# AD7606.net
KiCad netlist of a schematic drawn in Altium Designer
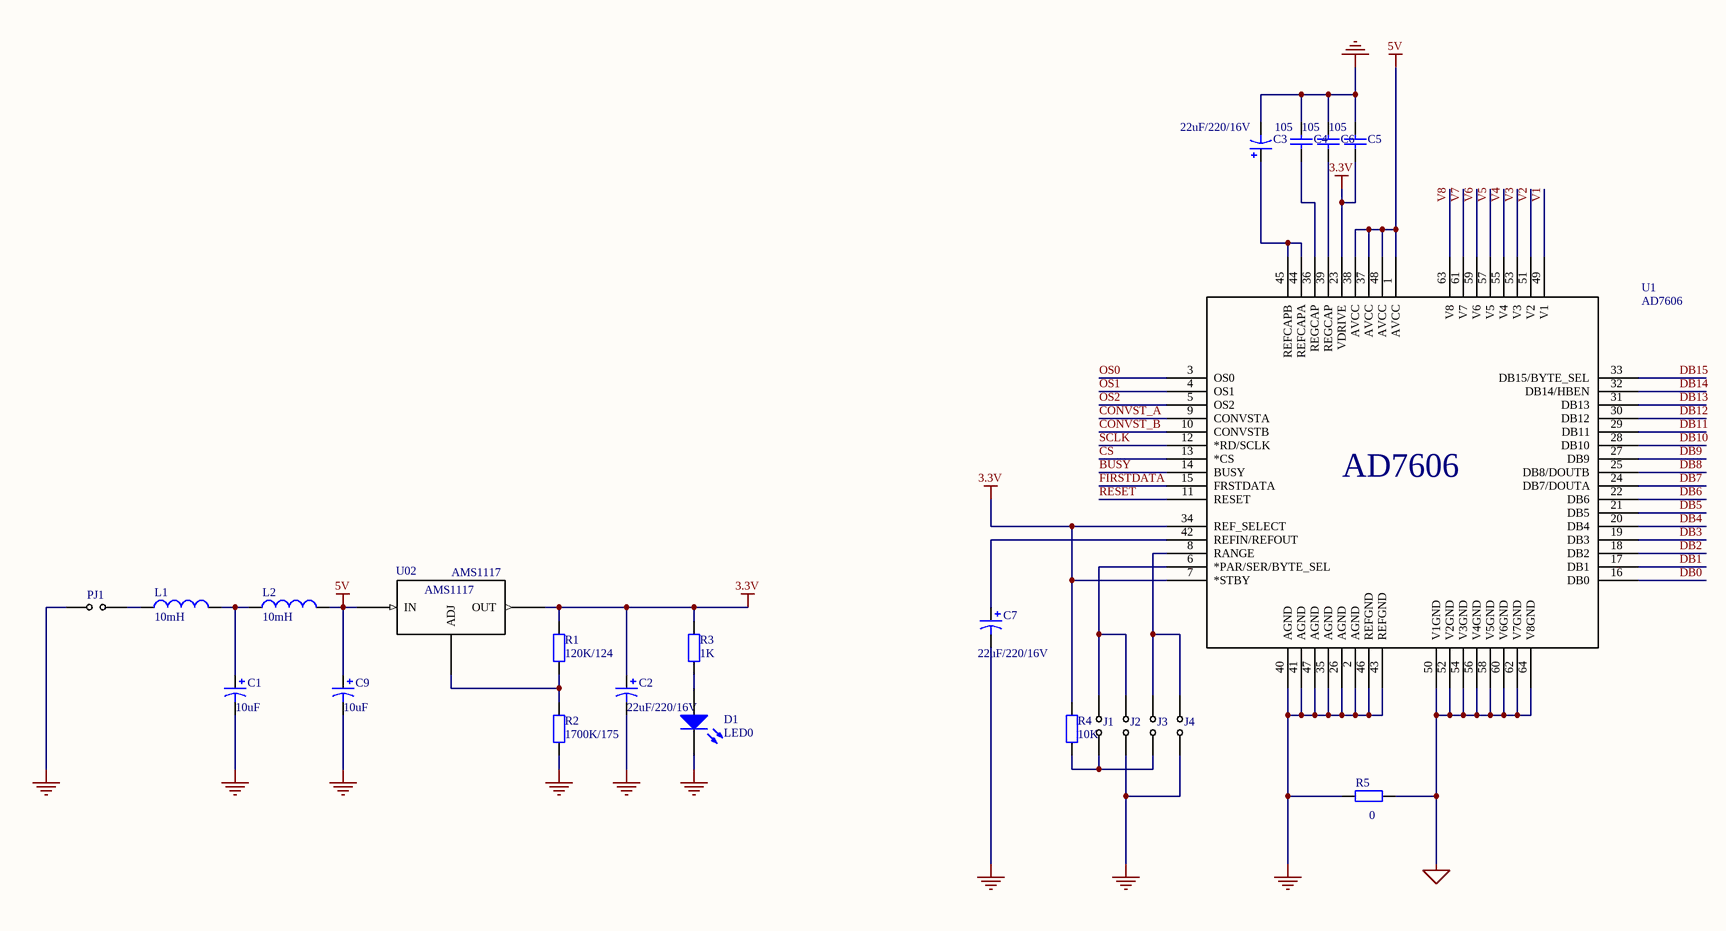
[diagram p0: AD7606.SchDoc]

(export (version "E")
  (design (tool "Eeschema 10.0.6"))
  (components
    (comp (ref "C1")
      (value "10uF")
      (footprint "TCAP_SMD_2312_6032-28_C_M")
      (description "Polarized Capacitor (Radial)")
      (fields (field (name "Comment") "Cap Pol1") (field (name "PUBLISHER") "Altium Limited"))
      (libsource (lib "Miscellaneous Devices") (part "Cap Pol1"))
    )
    (comp (ref "C2")
      (value "22uF/220/16V")
      (footprint "TCAP_SMD_2312_6032-28_C_M")
      (description "Polarized Capacitor (Radial)")
      (fields (field (name "Comment") "Cap Pol1") (field (name "PUBLISHER") "Altium Limited"))
      (libsource (lib "Miscellaneous Devices") (part "Cap Pol1"))
    )
    (comp (ref "C3")
      (value "22uF/220/16V")
      (footprint "TCAP_SMD_2312_6032-28_C_M")
      (description "Polarized Capacitor (Radial)")
      (fields (field (name "Comment") "Cap Pol1") (field (name "PUBLISHER") "Altium Limited"))
      (libsource (lib "Miscellaneous Devices") (part "Cap Pol1"))
    )
    (comp (ref "C4")
      (value "105")
      (footprint "CAP_SMD_1206_3216_M")
      (description "Capacitor")
      (fields (field (name "Comment") "Cap") (field (name "PUBLISHER") "Altium Limited"))
      (libsource (lib "Miscellaneous Devices") (part "Cap"))
    )
    (comp (ref "C5")
      (value "105")
      (footprint "CAP_SMD_1206_3216_M")
      (description "Capacitor")
      (fields (field (name "Comment") "Cap") (field (name "PUBLISHER") "Altium Limited"))
      (libsource (lib "Miscellaneous Devices") (part "Cap"))
    )
    (comp (ref "C6")
      (value "105")
      (footprint "CAP_SMD_1206_3216_M")
      (description "Capacitor")
      (fields (field (name "Comment") "Cap") (field (name "PUBLISHER") "Altium Limited"))
      (libsource (lib "Miscellaneous Devices") (part "Cap"))
    )
    (comp (ref "C7")
      (value "22uF/220/16V")
      (footprint "TCAP_SMD_2312_6032-28_C_M")
      (description "Polarized Capacitor (Radial)")
      (fields (field (name "Comment") "Cap Pol1") (field (name "PUBLISHER") "Altium Limited"))
      (libsource (lib "Miscellaneous Devices") (part "Cap Pol1"))
    )
    (comp (ref "C9")
      (value "10uF")
      (footprint "TCAP_SMD_2312_6032-28_C_M")
      (description "Polarized Capacitor (Radial)")
      (fields (field (name "Comment") "Cap Pol1") (field (name "PUBLISHER") "Altium Limited"))
      (libsource (lib "Miscellaneous Devices") (part "Cap Pol1"))
    )
    (comp (ref "D1")
      (value "LED0")
      (footprint "LED_SMD_0805_2012_M")
      (description "Typical INFRARED GaAs LED")
      (fields (field (name "PUBLISHER") "Altium Limited"))
      (libsource (lib "Miscellaneous Devices") (part "LED0"))
    )
    (comp (ref "J1") (value "head2") (footprint "HDR1X2") (libsource (lib "") (part "head2_1")))
    (comp (ref "J2") (value "head2") (footprint "HDR1X2") (libsource (lib "connectLib") (part "head2")))
    (comp (ref "J3") (value "head2") (footprint "HDR1X2") (libsource (lib "connectLib") (part "head2")))
    (comp (ref "J4") (value "head2") (footprint "HDR1X2") (libsource (lib "connectLib") (part "head2")))
    (comp (ref "L1")
      (value "10mH")
      (footprint "RES_SMD_0805_2012_M")
      (description "Inductor")
      (fields (field (name "PUBLISHER") "Altium Limited"))
      (libsource (lib "Miscellaneous Devices") (part "Inductor"))
    )
    (comp (ref "L2")
      (value "10mH")
      (footprint "RES_SMD_0805_2012_M")
      (description "Inductor")
      (fields (field (name "PUBLISHER") "Altium Limited"))
      (libsource (lib "Miscellaneous Devices") (part "Inductor"))
    )
    (comp (ref "PJ1") (value "head2") (footprint "HDR1X2") (libsource (lib "connectLib") (part "head2")))
    (comp (ref "R1")
      (value "120K/124")
      (footprint "RES_SMD_1206_3216_M")
      (description "Resistor")
      (fields (field (name "Comment") "Res2") (field (name "PUBLISHER") "Altium Limited"))
      (libsource (lib "") (part "Res2_1"))
    )
    (comp (ref "R2")
      (value "1700K/175")
      (footprint "RES_SMD_1206_3216_M")
      (description "Resistor")
      (fields (field (name "Comment") "Res2") (field (name "PUBLISHER") "Altium Limited"))
      (libsource (lib "") (part "Res2_1"))
    )
    (comp (ref "R3")
      (value "1K")
      (footprint "RES_SMD_1206_3216_M")
      (description "Resistor")
      (fields (field (name "Comment") "Res2") (field (name "PUBLISHER") "Altium Limited"))
      (libsource (lib "Miscellaneous Devices") (part "Res2"))
    )
    (comp (ref "R4")
      (value "10K")
      (footprint "RES_SMD_1206_3216_M")
      (description "Resistor")
      (fields (field (name "Comment") "Res2") (field (name "PUBLISHER") "Altium Limited"))
      (libsource (lib "") (part "Res2_1"))
    )
    (comp (ref "R5")
      (value "0")
      (footprint "RES_SMD_1206_3216_M")
      (description "Resistor")
      (fields (field (name "Comment") "Res2") (field (name "PUBLISHER") "Altium Limited"))
      (libsource (lib "") (part "Res2_2"))
    )
    (comp (ref "U1") (value "AD7606") (footprint "AD7606") (libsource (lib "multisupport") (part "AD7606")))
    (comp (ref "U02")
      (value "AMS1117")
      (footprint "SOT230P700X180-4N")
      (libsource (lib "chipslib") (part "AMS1117"))
    )
  )
  (nets
    (net (code "1") (name "/BUSY") (class "Default")
      (node (ref "U1") (pin "14") (pinfunction "BUSY_14") (pintype "passive"))
    )
    (net (code "2") (name "/CONVST_A") (class "Default")
      (node (ref "U1") (pin "9") (pinfunction "CONVSTA_9") (pintype "passive"))
    )
    (net (code "3") (name "/CONVST_B") (class "Default")
      (node (ref "U1") (pin "10") (pinfunction "CONVSTB_10") (pintype "passive"))
    )
    (net (code "4") (name "/CS") (class "Default")
      (node (ref "U1") (pin "13") (pinfunction "*CS_13") (pintype "passive"))
    )
    (net (code "5") (name "/DB0") (class "Default")
      (node (ref "U1") (pin "16") (pinfunction "DB0_16") (pintype "passive"))
    )
    (net (code "6") (name "/DB1") (class "Default")
      (node (ref "U1") (pin "17") (pinfunction "DB1_17") (pintype "passive"))
    )
    (net (code "7") (name "/DB2") (class "Default")
      (node (ref "U1") (pin "18") (pinfunction "DB2_18") (pintype "passive"))
    )
    (net (code "8") (name "/DB3") (class "Default")
      (node (ref "U1") (pin "19") (pinfunction "DB3_19") (pintype "passive"))
    )
    (net (code "9") (name "/DB4") (class "Default")
      (node (ref "U1") (pin "20") (pinfunction "DB4_20") (pintype "passive"))
    )
    (net (code "10") (name "/DB5") (class "Default")
      (node (ref "U1") (pin "21") (pinfunction "DB5_21") (pintype "passive"))
    )
    (net (code "11") (name "/DB6") (class "Default")
      (node (ref "U1") (pin "22") (pinfunction "DB6_22") (pintype "passive"))
    )
    (net (code "12") (name "/DB7") (class "Default")
      (node (ref "U1") (pin "24") (pinfunction "DB7/DOUTA_24") (pintype "passive"))
    )
    (net (code "13") (name "/DB8") (class "Default")
      (node (ref "U1") (pin "25") (pinfunction "DB8/DOUTB_25") (pintype "passive"))
    )
    (net (code "14") (name "/DB9") (class "Default")
      (node (ref "U1") (pin "27") (pinfunction "DB9_27") (pintype "passive"))
    )
    (net (code "15") (name "/DB10") (class "Default")
      (node (ref "U1") (pin "28") (pinfunction "DB10_28") (pintype "passive"))
    )
    (net (code "16") (name "/DB11") (class "Default")
      (node (ref "U1") (pin "29") (pinfunction "DB11_29") (pintype "passive"))
    )
    (net (code "17") (name "/DB12") (class "Default")
      (node (ref "U1") (pin "30") (pinfunction "DB12_30") (pintype "passive"))
    )
    (net (code "18") (name "/DB13") (class "Default")
      (node (ref "U1") (pin "31") (pinfunction "DB13_31") (pintype "passive"))
    )
    (net (code "19") (name "/DB14") (class "Default")
      (node (ref "U1") (pin "32") (pinfunction "DB14/HBEN_32") (pintype "passive"))
    )
    (net (code "20") (name "/DB15") (class "Default")
      (node (ref "U1") (pin "33") (pinfunction "DB15/BYTE_SEL_33") (pintype "passive"))
    )
    (net (code "21") (name "/FIRSTDATA") (class "Default")
      (node (ref "U1") (pin "15") (pinfunction "FRSTDATA_15") (pintype "passive"))
    )
    (net (code "22") (name "/OS0") (class "Default")
      (node (ref "U1") (pin "3") (pinfunction "OS0_3") (pintype "passive"))
    )
    (net (code "23") (name "/OS1") (class "Default")
      (node (ref "U1") (pin "4") (pinfunction "OS1_4") (pintype "passive"))
    )
    (net (code "24") (name "/OS2") (class "Default")
      (node (ref "U1") (pin "5") (pinfunction "OS2_5") (pintype "passive"))
    )
    (net (code "25") (name "/RESET") (class "Default")
      (node (ref "U1") (pin "11") (pinfunction "RESET_11") (pintype "passive"))
    )
    (net (code "26") (name "/SCLK") (class "Default")
      (node (ref "U1") (pin "12") (pinfunction "*RD/SCLK_12") (pintype "passive"))
    )
    (net (code "27") (name "/V1") (class "Default")
      (node (ref "U1") (pin "49") (pinfunction "V1_49") (pintype "passive"))
    )
    (net (code "28") (name "/V2") (class "Default")
      (node (ref "U1") (pin "51") (pinfunction "V2_51") (pintype "passive"))
    )
    (net (code "29") (name "/V3") (class "Default")
      (node (ref "U1") (pin "53") (pinfunction "V3_53") (pintype "passive"))
    )
    (net (code "30") (name "/V4") (class "Default")
      (node (ref "U1") (pin "55") (pinfunction "V4_55") (pintype "passive"))
    )
    (net (code "31") (name "/V5") (class "Default")
      (node (ref "U1") (pin "57") (pinfunction "V5_57") (pintype "passive"))
    )
    (net (code "32") (name "/V6") (class "Default")
      (node (ref "U1") (pin "59") (pinfunction "V6_59") (pintype "passive"))
    )
    (net (code "33") (name "/V7") (class "Default")
      (node (ref "U1") (pin "61") (pinfunction "V7_61") (pintype "passive"))
    )
    (net (code "34") (name "/V8") (class "Default")
      (node (ref "U1") (pin "63") (pinfunction "V8_63") (pintype "passive"))
    )
    (net (code "35") (name "3.3V") (class "Default")
      (node (ref "C2") (pin "1") (pinfunction "1_1") (pintype "passive"))
      (node (ref "C5") (pin "1") (pinfunction "1_1") (pintype "passive"))
      (node (ref "R1") (pin "2") (pinfunction "2_2") (pintype "passive"))
      (node (ref "R3") (pin "1") (pinfunction "1_1") (pintype "passive"))
      (node (ref "R4") (pin "2") (pinfunction "2_2") (pintype "passive"))
      (node (ref "U02") (pin "2") (pinfunction "OUT_2") (pintype "output"))
      (node (ref "U1") (pin "23") (pinfunction "VDRIVE_23") (pintype "passive"))
      (node (ref "U1") (pin "34") (pinfunction "REF_SELECT_34") (pintype "passive"))
      (node (ref "U1") (pin "7") (pinfunction "*STBY_7") (pintype "passive"))
    )
    (net (code "36") (name "5V") (class "Default")
      (node (ref "C9") (pin "1") (pinfunction "1_1") (pintype "passive"))
      (node (ref "L2") (pin "2") (pinfunction "2_2") (pintype "passive"))
      (node (ref "U02") (pin "3") (pinfunction "IN_3") (pintype "input"))
      (node (ref "U1") (pin "1") (pinfunction "AVCC_1") (pintype "passive"))
      (node (ref "U1") (pin "37") (pinfunction "AVCC_37") (pintype "passive"))
      (node (ref "U1") (pin "38") (pinfunction "AVCC_38") (pintype "passive"))
      (node (ref "U1") (pin "48") (pinfunction "AVCC_48") (pintype "passive"))
    )
    (net (code "37") (name "AGND") (class "Default")
      (node (ref "R5") (pin "2") (pinfunction "2_2") (pintype "passive"))
      (node (ref "U1") (pin "50") (pinfunction "V1GND_50") (pintype "passive"))
      (node (ref "U1") (pin "52") (pinfunction "V2GND_52") (pintype "passive"))
      (node (ref "U1") (pin "54") (pinfunction "V3GND_54") (pintype "passive"))
      (node (ref "U1") (pin "56") (pinfunction "V4GND_56") (pintype "passive"))
      (node (ref "U1") (pin "58") (pinfunction "V5GND_58") (pintype "passive"))
      (node (ref "U1") (pin "60") (pinfunction "V6GND_60") (pintype "passive"))
      (node (ref "U1") (pin "62") (pinfunction "V7GND_62") (pintype "passive"))
      (node (ref "U1") (pin "64") (pinfunction "V8GND_64") (pintype "passive"))
    )
    (net (code "38") (name "GND") (class "Default")
      (node (ref "C1") (pin "2") (pinfunction "2_2") (pintype "passive"))
      (node (ref "C2") (pin "2") (pinfunction "2_2") (pintype "passive"))
      (node (ref "C3") (pin "2") (pinfunction "2_2") (pintype "passive"))
      (node (ref "C4") (pin "2") (pinfunction "2_2") (pintype "passive"))
      (node (ref "C5") (pin "2") (pinfunction "2_2") (pintype "passive"))
      (node (ref "C6") (pin "2") (pinfunction "2_2") (pintype "passive"))
      (node (ref "C7") (pin "2") (pinfunction "2_2") (pintype "passive"))
      (node (ref "C9") (pin "2") (pinfunction "2_2") (pintype "passive"))
      (node (ref "D1") (pin "2") (pinfunction "K_2") (pintype "passive"))
      (node (ref "J2") (pin "1") (pinfunction "Vss_1") (pintype "power_in"))
      (node (ref "J4") (pin "1") (pinfunction "Vss_1") (pintype "power_in"))
      (node (ref "PJ1") (pin "1") (pinfunction "Vss_1") (pintype "power_in"))
      (node (ref "R2") (pin "1") (pinfunction "1_1") (pintype "passive"))
      (node (ref "R5") (pin "1") (pinfunction "1_1") (pintype "passive"))
      (node (ref "U1") (pin "2") (pinfunction "AGND_2") (pintype "passive"))
      (node (ref "U1") (pin "26") (pinfunction "AGND_26") (pintype "passive"))
      (node (ref "U1") (pin "35") (pinfunction "AGND_35") (pintype "passive"))
      (node (ref "U1") (pin "40") (pinfunction "AGND_40") (pintype "passive"))
      (node (ref "U1") (pin "41") (pinfunction "AGND_41") (pintype "passive"))
      (node (ref "U1") (pin "43") (pinfunction "REFGND_43") (pintype "passive"))
      (node (ref "U1") (pin "46") (pinfunction "REFGND_46") (pintype "passive"))
      (node (ref "U1") (pin "47") (pinfunction "AGND_47") (pintype "passive"))
    )
    (net (code "39") (name "Net-(C1-Pad1)") (class "Default")
      (node (ref "C1") (pin "1") (pinfunction "1_1") (pintype "passive"))
      (node (ref "L1") (pin "2") (pinfunction "2_2") (pintype "passive"))
      (node (ref "L2") (pin "1") (pinfunction "1_1") (pintype "passive"))
    )
    (net (code "40") (name "Net-(C4-Pad1)") (class "Default")
      (node (ref "C4") (pin "1") (pinfunction "1_1") (pintype "passive"))
      (node (ref "U1") (pin "36") (pinfunction "REGCAP_36") (pintype "passive"))
    )
    (net (code "41") (name "Net-(C6-Pad1)") (class "Default")
      (node (ref "C6") (pin "1") (pinfunction "1_1") (pintype "passive"))
      (node (ref "U1") (pin "39") (pinfunction "REGCAP_39") (pintype "passive"))
    )
    (net (code "42") (name "Net-(D1-A)") (class "Default")
      (node (ref "D1") (pin "1") (pinfunction "A_1") (pintype "passive"))
      (node (ref "R3") (pin "2") (pinfunction "2_2") (pintype "passive"))
    )
    (net (code "43") (name "Net-(J1-Vss-Pad2)") (class "Default")
      (node (ref "J1") (pin "2") (pinfunction "Vss_2") (pintype "passive"))
      (node (ref "J3") (pin "1") (pinfunction "Vss_1") (pintype "power_in"))
      (node (ref "R4") (pin "1") (pinfunction "1_1") (pintype "passive"))
    )
    (net (code "44") (name "Net-(L1-Pad1)") (class "Default")
      (node (ref "L1") (pin "1") (pinfunction "1_1") (pintype "passive"))
      (node (ref "PJ1") (pin "2") (pinfunction "Vss_2") (pintype "passive"))
    )
    (net (code "45") (name "Net-(U1-*PAR{slash}SER{slash}BYTE_SEL)") (class "Default")
      (node (ref "J1") (pin "1") (pinfunction "Vss_1") (pintype "power_in"))
      (node (ref "J2") (pin "2") (pinfunction "Vss_2") (pintype "passive"))
      (node (ref "U1") (pin "6") (pinfunction "*PAR/SER/BYTE_SEL_6") (pintype "passive"))
    )
    (net (code "46") (name "Net-(U1-RANGE)") (class "Default")
      (node (ref "J3") (pin "2") (pinfunction "Vss_2") (pintype "passive"))
      (node (ref "J4") (pin "2") (pinfunction "Vss_2") (pintype "passive"))
      (node (ref "U1") (pin "8") (pinfunction "RANGE_8") (pintype "passive"))
    )
    (net (code "47") (name "Net-(U1-REFCAPA)") (class "Default")
      (node (ref "C3") (pin "1") (pinfunction "1_1") (pintype "passive"))
      (node (ref "U1") (pin "44") (pinfunction "REFCAPA_44") (pintype "passive"))
      (node (ref "U1") (pin "45") (pinfunction "REFCAPB_45") (pintype "passive"))
    )
    (net (code "48") (name "Net-(U1-REFIN{slash}REFOUT)") (class "Default")
      (node (ref "C7") (pin "1") (pinfunction "1_1") (pintype "passive"))
      (node (ref "U1") (pin "42") (pinfunction "REFIN/REFOUT_42") (pintype "passive"))
    )
    (net (code "49") (name "Net-(U02-ADJ)") (class "Default")
      (node (ref "R1") (pin "1") (pinfunction "1_1") (pintype "passive"))
      (node (ref "R2") (pin "2") (pinfunction "2_2") (pintype "passive"))
      (node (ref "U02") (pin "1") (pinfunction "ADJ_1") (pintype "power_in"))
    )
  )
)
